# UVLO_MODULE_TOP.net
KiCad netlist of a schematic drawn in Altium Designer
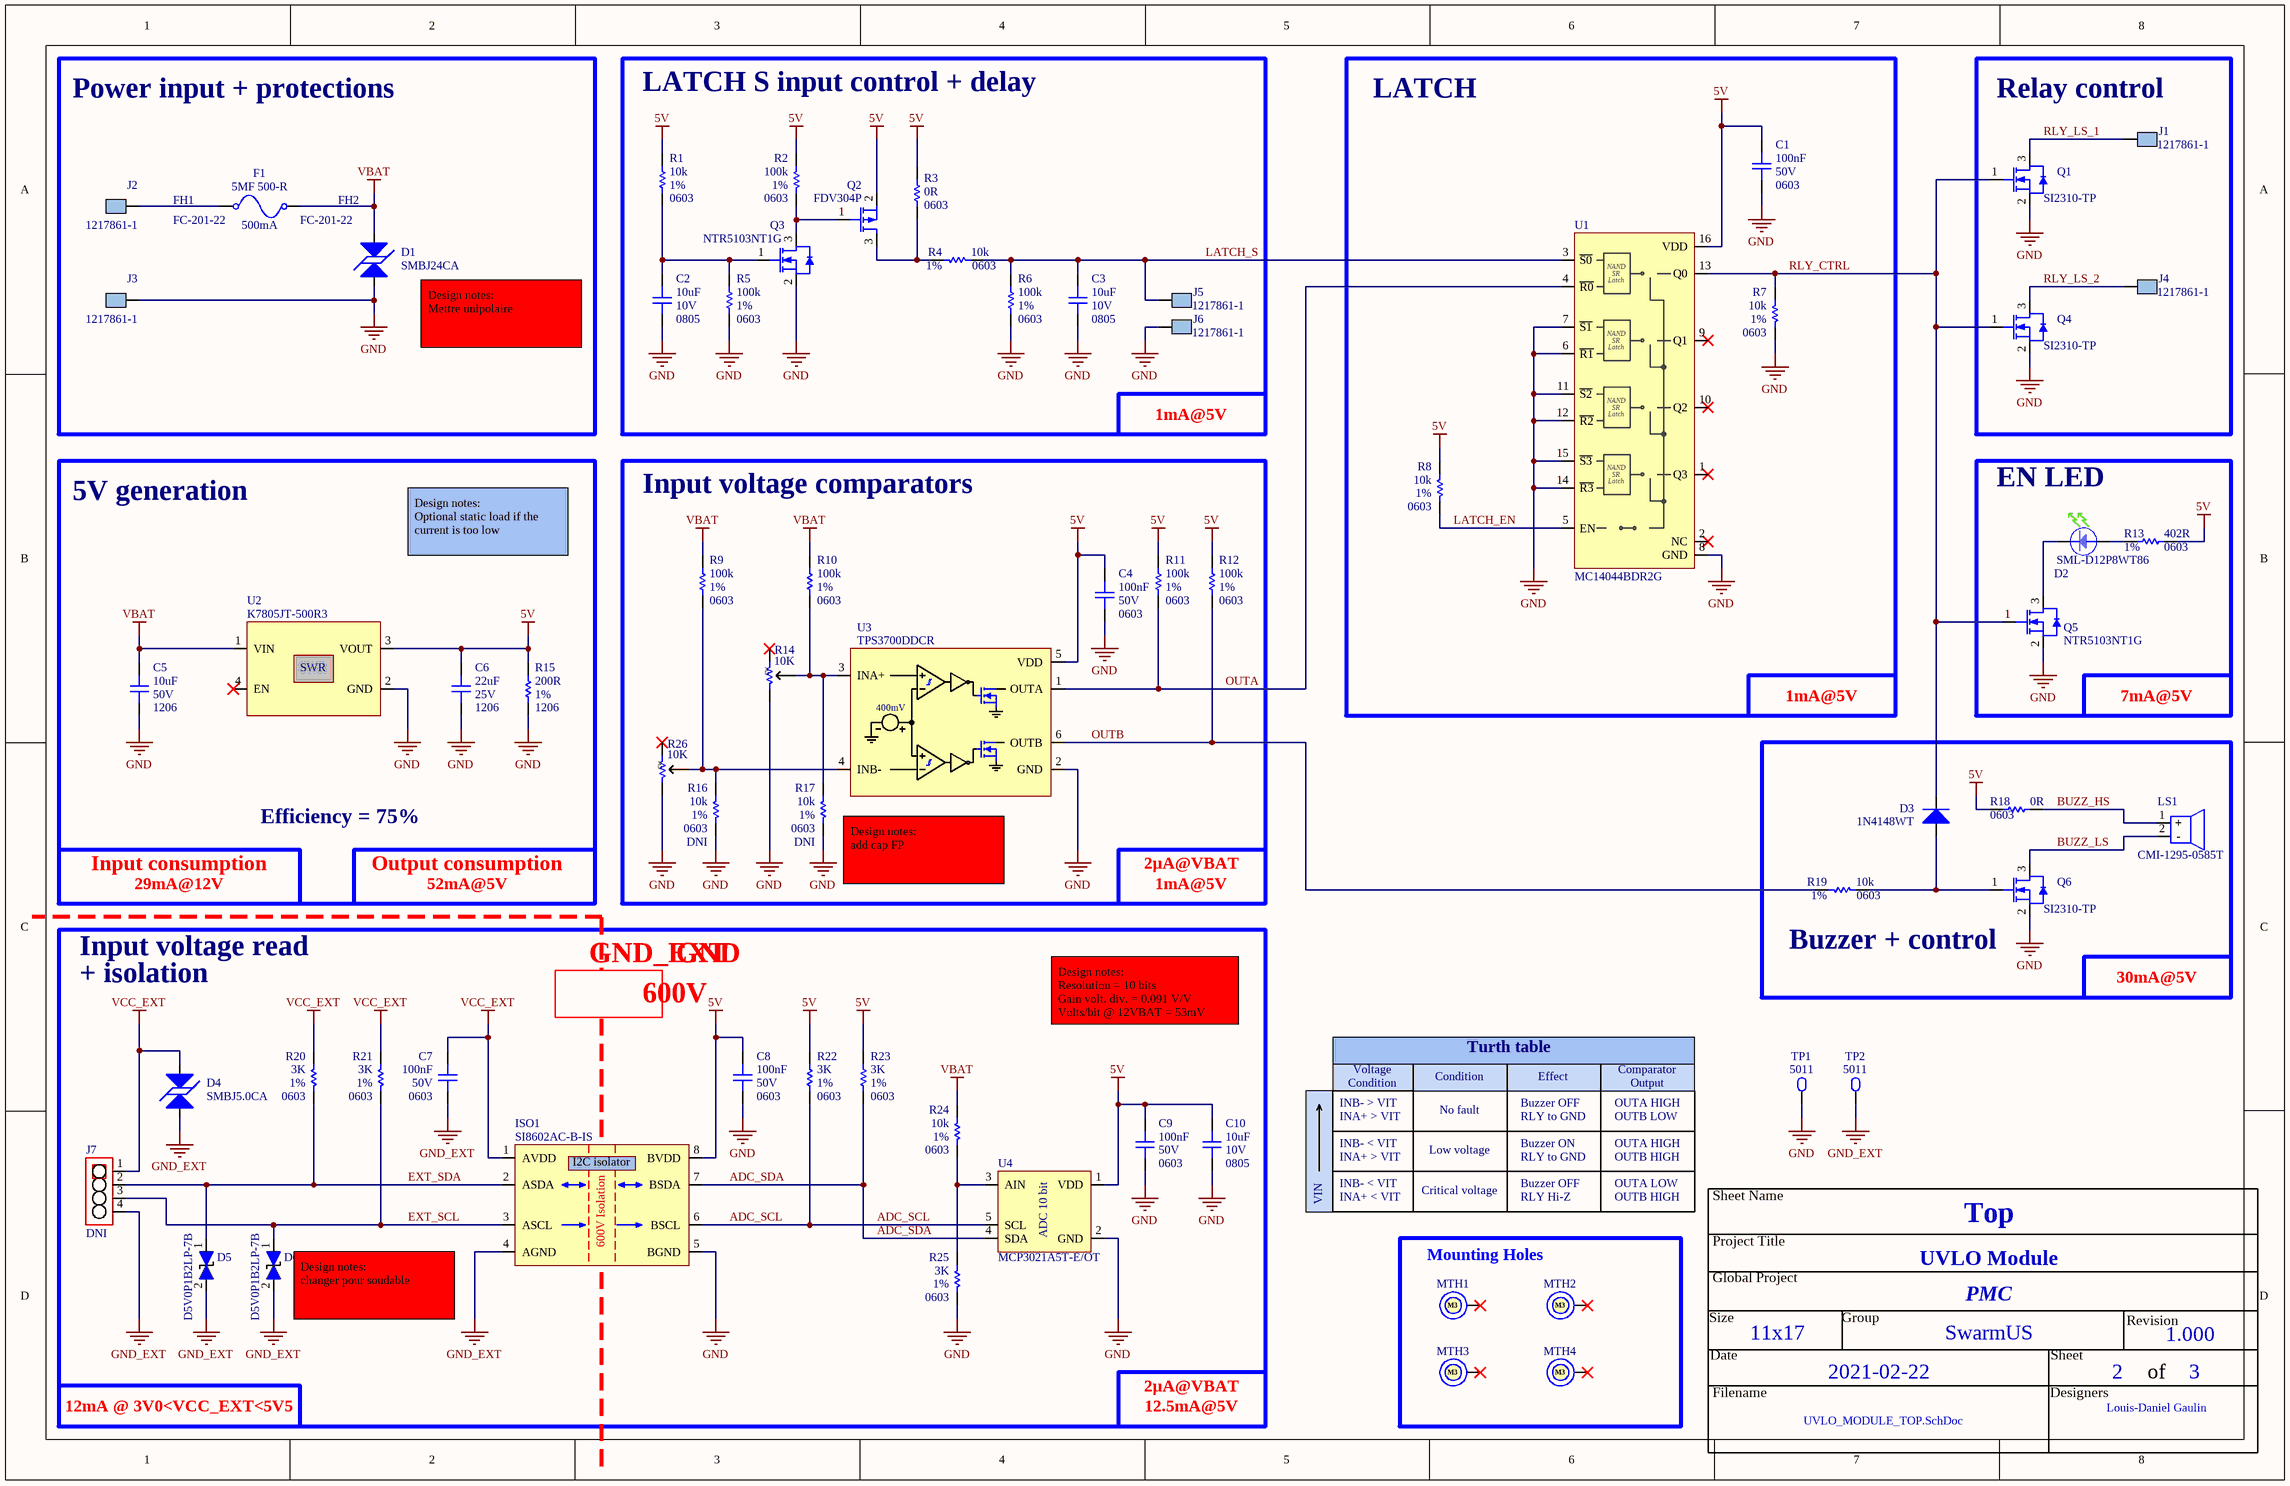
[diagram p0: UVLO_MODULE_TOP.SchDoc]

(export (version "E")
  (design (tool "Eeschema 10.0.6"))
  (components
    (comp (ref "C1")
      (value "100nF")
      (footprint "CAP_CER_0603")
      (description "CAP - CER 100nF 50V X7R - 0603")
      (fields
        (field (name "TOLERANCE") "10%")
        (field (name "PACKAGE") "0603")
        (field (name "VOLTAGE RATING") "50V")
        (field (name "Comment") "CC0603KRX7R9BB104")
        (field (name "CREATEDBY/DATE") "Louis-Daniel Gaulin / 25-02-2021")
        (field (name "VERIFIEDBY") "Hubert Dube - 26/02/2021")
      )
      (libsource (lib "SWARMUS_LIB") (part "CAP_CER_CC0603KRX7R9BB104"))
    )
    (comp (ref "C2")
      (value "10uF")
      (footprint "CAP_CER_0805")
      (description "CAP - CER 10UF 10% 10V X5R - 0805")
      (fields
        (field (name "TOLERANCE") "10%")
        (field (name "PACKAGE") "0805")
        (field (name "VOLTAGE RATING") "10V")
        (field (name "Comment") "LMK212BJ106KG-T")
        (field (name "CREATEDBY/DATE") "Caroline Paulin / 25 juillet 2018")
        (field (name "VERIFIEDBY") "Nicolas V. (2019-01-22)")
      )
      (libsource (lib "GRAMS_MASTER_LIB") (part "CAP_CER_LMK212BJ106KG-T"))
    )
    (comp (ref "C3")
      (value "10uF")
      (footprint "CAP_CER_0805")
      (description "CAP - CER 10UF 10% 10V X5R - 0805")
      (fields
        (field (name "TOLERANCE") "10%")
        (field (name "PACKAGE") "0805")
        (field (name "VOLTAGE RATING") "10V")
        (field (name "Comment") "LMK212BJ106KG-T")
        (field (name "CREATEDBY/DATE") "Caroline Paulin / 25 juillet 2018")
        (field (name "VERIFIEDBY") "Nicolas V. (2019-01-22)")
      )
      (libsource (lib "GRAMS_MASTER_LIB") (part "CAP_CER_LMK212BJ106KG-T"))
    )
    (comp (ref "C4")
      (value "100nF")
      (footprint "CAP_CER_0603")
      (description "CAP - CER 100nF 50V X7R - 0603")
      (fields
        (field (name "TOLERANCE") "10%")
        (field (name "PACKAGE") "0603")
        (field (name "VOLTAGE RATING") "50V")
        (field (name "Comment") "CC0603KRX7R9BB104")
        (field (name "CREATEDBY/DATE") "Louis-Daniel Gaulin / 25-02-2021")
        (field (name "VERIFIEDBY") "Hubert Dube - 26/02/2021")
      )
      (libsource (lib "SWARMUS_LIB") (part "CAP_CER_CC0603KRX7R9BB104"))
    )
    (comp (ref "C5")
      (value "10uF")
      (footprint "CAP_CER_1206")
      (description "CAP - CER 10UF 10% 50V X5R - 1206")
      (fields
        (field (name "TOLERANCE") "10%")
        (field (name "PACKAGE") "1206")
        (field (name "VOLTAGE RATING") "50V")
        (field (name "Comment") "GRT31CR61H106KE01L")
        (field (name "CREATEDBY/DATE") "Nicolas Roy - 2018/12/19")
        (field (name "VERIFIEDBY") "Nicolas V. (2019-01-22)")
      )
      (libsource (lib "GRAMS_MASTER_LIB") (part "CAP_CER_GRT31CR61H106KE01L"))
    )
    (comp (ref "C6")
      (value "22uF")
      (footprint "CAP_CER_1206")
      (description "CAP - CER 22uF 10% 25V X5R - 1206")
      (fields
        (field (name "TOLERANCE") "10%")
        (field (name "PACKAGE") "1206")
        (field (name "VOLTAGE RATING") "25V")
        (field (name "Comment") "CL31A226KAHNNNE")
        (field (name "CREATEDBY/DATE") "Philippe Arsenault/21 Janvier 2020")
        (field (name "VERIFIEDBY") "C.Paulin - 28/01/2020")
      )
      (libsource (lib "GRAMS_MASTER_LIB") (part "CAP_CER_CL31A226KAHNNNE"))
    )
    (comp (ref "C7")
      (value "100nF")
      (footprint "CAP_CER_0603")
      (description "CAP - CER 100nF 50V X7R - 0603")
      (fields
        (field (name "TOLERANCE") "10%")
        (field (name "PACKAGE") "0603")
        (field (name "VOLTAGE RATING") "50V")
        (field (name "Comment") "CC0603KRX7R9BB104")
        (field (name "CREATEDBY/DATE") "Louis-Daniel Gaulin / 25-02-2021")
        (field (name "VERIFIEDBY") "Hubert Dube - 26/02/2021")
      )
      (libsource (lib "SWARMUS_LIB") (part "CAP_CER_CC0603KRX7R9BB104"))
    )
    (comp (ref "C8")
      (value "100nF")
      (footprint "CAP_CER_0603")
      (description "CAP - CER 100nF 50V X7R - 0603")
      (fields
        (field (name "TOLERANCE") "10%")
        (field (name "PACKAGE") "0603")
        (field (name "VOLTAGE RATING") "50V")
        (field (name "Comment") "CC0603KRX7R9BB104")
        (field (name "CREATEDBY/DATE") "Louis-Daniel Gaulin / 25-02-2021")
        (field (name "VERIFIEDBY") "Hubert Dube - 26/02/2021")
      )
      (libsource (lib "SWARMUS_LIB") (part "CAP_CER_CC0603KRX7R9BB104"))
    )
    (comp (ref "C9")
      (value "100nF")
      (footprint "CAP_CER_0603")
      (description "CAP - CER 100nF 50V X7R - 0603")
      (fields
        (field (name "TOLERANCE") "10%")
        (field (name "PACKAGE") "0603")
        (field (name "VOLTAGE RATING") "50V")
        (field (name "Comment") "CC0603KRX7R9BB104")
        (field (name "CREATEDBY/DATE") "Louis-Daniel Gaulin / 25-02-2021")
        (field (name "VERIFIEDBY") "Hubert Dube - 26/02/2021")
      )
      (libsource (lib "SWARMUS_LIB") (part "CAP_CER_CC0603KRX7R9BB104"))
    )
    (comp (ref "C10")
      (value "10uF")
      (footprint "CAP_CER_0805")
      (description "CAP - CER 10UF 10% 10V X5R - 0805")
      (fields
        (field (name "TOLERANCE") "10%")
        (field (name "PACKAGE") "0805")
        (field (name "VOLTAGE RATING") "10V")
        (field (name "Comment") "LMK212BJ106KG-T")
        (field (name "CREATEDBY/DATE") "Caroline Paulin / 25 juillet 2018")
        (field (name "VERIFIEDBY") "Nicolas V. (2019-01-22)")
      )
      (libsource (lib "GRAMS_MASTER_LIB") (part "CAP_CER_LMK212BJ106KG-T"))
    )
    (comp (ref "D1")
      (value "SMBJ24CA")
      (footprint "TVS_PWR_SMBJ36CA")
      (description "TVS - 24V 26.7V 600W - DO214AA")
      (fields
        (field (name "CREATEDBY/DATE") "Arnaud Samson - 06/07/18")
        (field (name "VERIFIEDBY") "Jonathan Bouchard - 2018-07-13")
      )
      (libsource (lib "GRAMS_MASTER_LIB") (part "TVS_PWR_SMBJ24CA"))
    )
    (comp (ref "D2")
      (value "SML-D12P8WT86")
      (footprint "LED_SML-D12P8WT86")
      (description "LED - GREEN DIFFUSED 0603 SMD - 0603")
      (fields
        (field (name "CREATEDBY/DATE") "Keven Deslandes - 2018/11/21")
        (field (name "VERIFIEDBY") "Caroline Paulin - 13 février 2019")
      )
      (libsource (lib "GRAMS_MASTER_LIB") (part "LED_SML-D12P8WT86"))
    )
    (comp (ref "D3")
      (value "1N4148WT")
      (footprint "DIO_1N4148WT")
      (description "DIO - 1N4148WT - SOD-523F")
      (fields
        (field (name "CREATEDBY/DATE") "Joel Lemay 2018-06-15")
        (field (name "VERIFIEDBY") "Arnaud Samson 17-07-18")
      )
      (libsource (lib "GRAMS_MASTER_LIB") (part "DIO_1N4148WT"))
    )
    (comp (ref "D4")
      (value "SMBJ5.0CA")
      (footprint "TVS_PWR_SMBJ5.0CA")
      (description "TVS - BIDIR 5V 9.2V 600W - DO214AA")
      (fields
        (field (name "CREATEDBY/DATE") "Jonathan Bouchard - 2019-03-22")
        (field (name "VERIFIEDBY") "Nicolas V. (2019-05-06)")
      )
      (libsource (lib "GRAMS_MASTER_LIB") (part "TVS_PWR_SMBJ5.0CA"))
    )
    (comp (ref "D5")
      (value "D5V0P1B2LP-7B")
      (footprint "TVS_DATA_D5V0P1B2LP-7B")
      (description "TVS - TVS DIODE 5.5V 13V - 0402")
      (fields
        (field (name "CREATEDBY/DATE") "Keven Deslandes - 2018/10/19")
        (field (name "VERIFIEDBY") "Caroline Paulin -28 janvier 2018")
      )
      (libsource (lib "GRAMS_MASTER_LIB") (part "TVS_DATA_D5V0P1B2LP-7B"))
    )
    (comp (ref "D6")
      (value "D5V0P1B2LP-7B")
      (footprint "TVS_DATA_D5V0P1B2LP-7B")
      (description "TVS - TVS DIODE 5.5V 13V - 0402")
      (fields
        (field (name "CREATEDBY/DATE") "Keven Deslandes - 2018/10/19")
        (field (name "VERIFIEDBY") "Caroline Paulin -28 janvier 2018")
      )
      (libsource (lib "GRAMS_MASTER_LIB") (part "TVS_DATA_D5V0P1B2LP-7B"))
    )
    (comp (ref "F1")
      (value "5MF 500-R")
      (footprint "FUS_5MF 500-R")
      (description "FUS - CARTRIDGE GLASS 500mA 250VAC/125VDC - 5X20mm")
      (fields
        (field (name "CURRENT RATING") "500mA")
        (field (name "CREATEDBY/DATE") "Louis-Daniel Gaulin")
        (field (name "VERIFIEDBY") "Hubert Dube - 26/02/2021")
      )
      (libsource (lib "SWARMUS_LIB") (part "FUS_5MF 500-R"))
    )
    (comp (ref "FH1")
      (value "FC-201-22")
      (footprint "FHO_FC-201-22")
      (description "FHO - FUSE CLIP 5mm CARTRIDGE 10A PCB - 2-TH")
      (fields
        (field (name "CREATEDBY/DATE") "Louis-Daniel Gaulin / 26-02-2021")
        (field (name "VERIFIEDBY") "Hubert Dube - 26/02/2021")
      )
      (libsource (lib "SWARMUS_LIB") (part "FHO_FC-201-22"))
    )
    (comp (ref "FH2")
      (value "FC-201-22")
      (footprint "FHO_FC-201-22")
      (description "FHO - FUSE CLIP 5mm CARTRIDGE 10A PCB - 2-TH")
      (fields
        (field (name "CREATEDBY/DATE") "Louis-Daniel Gaulin / 26-02-2021")
        (field (name "VERIFIEDBY") "Hubert Dube - 26/02/2021")
      )
      (libsource (lib "SWARMUS_LIB") (part "FHO_FC-201-22"))
    )
    (comp (ref "ISO1")
      (value "SI8602AC-B-IS")
      (footprint "ISO_SI8602AC-B-IS")
      (description "ISO - DGTL ISO 600V 2CH I2C  - 8-SOIC")
      (fields
        (field (name "CREATEDBY/DATE") "Louis-Daniel Gaulin / 25-02-2021")
        (field (name "VERIFIEDBY") "Hubert Dube - 26/02/2021")
      )
      (libsource (lib "SWARMUS_LIB") (part "ISO_SI8602AC-B-IS"))
    )
    (comp (ref "J1")
      (value "1217861-1")
      (footprint "CON_1217861-1")
      (description "CON - Quick connect tab - TH")
      (fields
        (field (name "CREATEDBY/DATE") "Louis-Daniel Gaulin / 24-02-2021")
        (field (name "VERIFIEDBY") "Hubert Dube - 26/02/2021")
      )
      (libsource (lib "SWARMUS_LIB") (part "CON_1217861-1"))
    )
    (comp (ref "J2")
      (value "1217861-1")
      (footprint "CON_1217861-1")
      (description "CON - Quick connect tab - TH")
      (fields
        (field (name "CREATEDBY/DATE") "Louis-Daniel Gaulin / 24-02-2021")
        (field (name "VERIFIEDBY") "Hubert Dube - 26/02/2021")
      )
      (libsource (lib "") (part "CON_1217861-1_1"))
    )
    (comp (ref "J3")
      (value "1217861-1")
      (footprint "CON_1217861-1")
      (description "CON - Quick connect tab - TH")
      (fields
        (field (name "CREATEDBY/DATE") "Louis-Daniel Gaulin / 24-02-2021")
        (field (name "VERIFIEDBY") "Hubert Dube - 26/02/2021")
      )
      (libsource (lib "") (part "CON_1217861-1_1"))
    )
    (comp (ref "J4")
      (value "1217861-1")
      (footprint "CON_1217861-1")
      (description "CON - Quick connect tab - TH")
      (fields
        (field (name "CREATEDBY/DATE") "Louis-Daniel Gaulin / 24-02-2021")
        (field (name "VERIFIEDBY") "Hubert Dube - 26/02/2021")
      )
      (libsource (lib "SWARMUS_LIB") (part "CON_1217861-1"))
    )
    (comp (ref "J5")
      (value "1217861-1")
      (footprint "CON_1217861-1")
      (description "CON - Quick connect tab - TH")
      (fields
        (field (name "CREATEDBY/DATE") "Louis-Daniel Gaulin / 24-02-2021")
        (field (name "VERIFIEDBY") "Hubert Dube - 26/02/2021")
      )
      (libsource (lib "SWARMUS_LIB") (part "CON_1217861-1"))
    )
    (comp (ref "J6")
      (value "1217861-1")
      (footprint "CON_1217861-1")
      (description "CON - Quick connect tab - TH")
      (fields
        (field (name "CREATEDBY/DATE") "Louis-Daniel Gaulin / 24-02-2021")
        (field (name "VERIFIEDBY") "Hubert Dube - 26/02/2021")
      )
      (libsource (lib "SWARMUS_LIB") (part "CON_1217861-1"))
    )
    (comp (ref "J7")
      (value "CON_HDR_1X4")
      (footprint "CON_HDR_1X4")
      (description "CON - Header 1X4 pins, 100Mils - TH-4")
      (fields
        (field (name "ASSEMBLY NOTE") "DNI")
        (field (name "CREATEDBY/DATE") "Nicolas V (2020-02-24)")
        (field (name "VERIFIEDBY") "Nicolas V (2020-02-24)")
      )
      (libsource (lib "GRAMS_MASTER_LIB") (part "CON_HDR_1X4"))
    )
    (comp (ref "LS1")
      (value "CMI-1295-0585T")
      (footprint "UND_SPK_CMI-1295-0585T")
      (description "LS - Buzzer indicator 5V 30mA 2.3kHz 85dB - TH")
      (fields
        (field (name "CREATEDBY/DATE") "Louis-Daniel Gaulin / 24-02-2021")
        (field (name "VERIFIEDBY") "Hubert Dube - 26/02/2021")
      )
      (libsource (lib "SWARMUS_LIB") (part "UND_LS_CMI-1295-0585T"))
    )
    (comp (ref "MTH1")
      (value "M3")
      (footprint "MTH_M3")
      (description "MTH - MOUNTING HOLE M3 PLATED - M3")
      (fields
        (field (name "CREATEDBY/DATE") "Jonathan Bouchard 2018-07-23")
        (field (name "VERIFIEDBY") "Arnaud Samson 23-07-18")
      )
      (libsource (lib "GRAMS_MASTER_LIB") (part "MTH_M3"))
    )
    (comp (ref "MTH2")
      (value "M3")
      (footprint "MTH_M3")
      (description "MTH - MOUNTING HOLE M3 PLATED - M3")
      (fields
        (field (name "CREATEDBY/DATE") "Jonathan Bouchard 2018-07-23")
        (field (name "VERIFIEDBY") "Arnaud Samson 23-07-18")
      )
      (libsource (lib "GRAMS_MASTER_LIB") (part "MTH_M3"))
    )
    (comp (ref "MTH3")
      (value "M3")
      (footprint "MTH_M3")
      (description "MTH - MOUNTING HOLE M3 PLATED - M3")
      (fields
        (field (name "CREATEDBY/DATE") "Jonathan Bouchard 2018-07-23")
        (field (name "VERIFIEDBY") "Arnaud Samson 23-07-18")
      )
      (libsource (lib "GRAMS_MASTER_LIB") (part "MTH_M3"))
    )
    (comp (ref "MTH4")
      (value "M3")
      (footprint "MTH_M3")
      (description "MTH - MOUNTING HOLE M3 PLATED - M3")
      (fields
        (field (name "CREATEDBY/DATE") "Jonathan Bouchard 2018-07-23")
        (field (name "VERIFIEDBY") "Arnaud Samson 23-07-18")
      )
      (libsource (lib "GRAMS_MASTER_LIB") (part "MTH_M3"))
    )
    (comp (ref "Q1")
      (value "SI2310-TP")
      (footprint "TRX_NMOS_SI2310-TP")
      (description "TRX - MOSFET N-CH 60V 3A - SOT-23")
      (fields
        (field (name "CREATEDBY/DATE") "Louis-Daniel Gaulin / 20-02-2020")
        (field (name "VERIFIEDBY") "C.Paulin - 21/02/2020")
      )
      (libsource (lib "GRAMS_MASTER_LIB") (part "TRX_NMOS_SI2310-TP"))
    )
    (comp (ref "Q2")
      (value "FDV304P")
      (footprint "TRX_PMOS_FDV304P")
      (description "TRX - PMOS 25V 460MA - SOT−23")
      (fields
        (field (name "CREATEDBY/DATE") "Joel Lemay 2018-07-20")
        (field (name "VERIFIEDBY") "Caroline Paulin - 6 sept 2018")
      )
      (libsource (lib "GRAMS_MASTER_LIB") (part "TRX_PMOS_FDV304P"))
    )
    (comp (ref "Q3")
      (value "NTR5103NT1G")
      (footprint "TRX_NMOS_NTR5103NT1G")
      (description "TRX - MOSFET N-CH 60V 0.26A- SOT-23-3")
      (fields
        (field (name "CREATEDBY/DATE") "Olivier Bernard / 7/5/2017")
        (field (name "VERIFIEDBY") "Caroline Paulin / 10 juillet 2018")
      )
      (libsource (lib "GRAMS_MASTER_LIB") (part "TRX_NMOS_NTR5103NT1G"))
    )
    (comp (ref "Q4")
      (value "SI2310-TP")
      (footprint "TRX_NMOS_SI2310-TP")
      (description "TRX - MOSFET N-CH 60V 3A - SOT-23")
      (fields
        (field (name "CREATEDBY/DATE") "Louis-Daniel Gaulin / 20-02-2020")
        (field (name "VERIFIEDBY") "C.Paulin - 21/02/2020")
      )
      (libsource (lib "GRAMS_MASTER_LIB") (part "TRX_NMOS_SI2310-TP"))
    )
    (comp (ref "Q5")
      (value "NTR5103NT1G")
      (footprint "TRX_NMOS_NTR5103NT1G")
      (description "TRX - MOSFET N-CH 60V 0.26A- SOT-23-3")
      (fields
        (field (name "CREATEDBY/DATE") "Olivier Bernard / 7/5/2017")
        (field (name "VERIFIEDBY") "Caroline Paulin / 10 juillet 2018")
      )
      (libsource (lib "GRAMS_MASTER_LIB") (part "TRX_NMOS_NTR5103NT1G"))
    )
    (comp (ref "Q6")
      (value "SI2310-TP")
      (footprint "TRX_NMOS_SI2310-TP")
      (description "TRX - MOSFET N-CH 60V 3A - SOT-23")
      (fields
        (field (name "CREATEDBY/DATE") "Louis-Daniel Gaulin / 20-02-2020")
        (field (name "VERIFIEDBY") "C.Paulin - 21/02/2020")
      )
      (libsource (lib "GRAMS_MASTER_LIB") (part "TRX_NMOS_SI2310-TP"))
    )
    (comp (ref "R1")
      (value "10k")
      (footprint "RES_0603")
      (description "RES - 10k 1% 1/10W - 0603")
      (fields
        (field (name "TOLERANCE") "1%")
        (field (name "PACKAGE") "0603")
        (field (name "Comment") "RC0603FR-0710KL")
        (field (name "CREATEDBY/DATE") "Louis-Daniel Gaulin / 24-02-2021")
        (field (name "VERIFIEDBY") "Hubert Dube - 26/02/2021")
      )
      (libsource (lib "SWARMUS_LIB") (part "RES_RC0603FR-0710KL"))
    )
    (comp (ref "R2")
      (value "100k")
      (footprint "RES_0603")
      (description "RES - 100k 1% 1/10W - 0603")
      (fields
        (field (name "TOLERANCE") "1%")
        (field (name "PACKAGE") "0603")
        (field (name "Comment") "RC0603FR-07100KL")
        (field (name "CREATEDBY/DATE") "Louis-Daniel Gaulin / 24-02-2021")
        (field (name "VERIFIEDBY") "Hubert Dube")
      )
      (libsource (lib "SWARMUS_LIB") (part "RES_RC0603FR-07100KL"))
    )
    (comp (ref "R3")
      (value "0R")
      (footprint "RES_0603")
      (description "RES - 0 ohm jumper 1/10W - 0603")
      (fields
        (field (name "PACKAGE") "0603")
        (field (name "Comment") "RC0603JR-070RL")
        (field (name "CREATEDBY/DATE") "L-P Gauthier 2018-10-30")
        (field (name "VERIFIEDBY") "Caroline Paulin  - 5/11/2018")
      )
      (libsource (lib "GRAMS_MASTER_LIB") (part "RES_RC0603JR-070RL"))
    )
    (comp (ref "R4")
      (value "10k")
      (footprint "RES_0603")
      (description "RES - 10k 1% 1/10W - 0603")
      (fields
        (field (name "TOLERANCE") "1%")
        (field (name "PACKAGE") "0603")
        (field (name "Comment") "RC0603FR-0710KL")
        (field (name "CREATEDBY/DATE") "Louis-Daniel Gaulin / 24-02-2021")
        (field (name "VERIFIEDBY") "Hubert Dube - 26/02/2021")
      )
      (libsource (lib "SWARMUS_LIB") (part "RES_RC0603FR-0710KL"))
    )
    (comp (ref "R5")
      (value "100k")
      (footprint "RES_0603")
      (description "RES - 100k 1% 1/10W - 0603")
      (fields
        (field (name "TOLERANCE") "1%")
        (field (name "PACKAGE") "0603")
        (field (name "Comment") "RC0603FR-07100KL")
        (field (name "CREATEDBY/DATE") "Louis-Daniel Gaulin / 24-02-2021")
        (field (name "VERIFIEDBY") "Hubert Dube")
      )
      (libsource (lib "SWARMUS_LIB") (part "RES_RC0603FR-07100KL"))
    )
    (comp (ref "R6")
      (value "100k")
      (footprint "RES_0603")
      (description "RES - 100k 1% 1/10W - 0603")
      (fields
        (field (name "TOLERANCE") "1%")
        (field (name "PACKAGE") "0603")
        (field (name "Comment") "RC0603FR-07100KL")
        (field (name "CREATEDBY/DATE") "Louis-Daniel Gaulin / 24-02-2021")
        (field (name "VERIFIEDBY") "Hubert Dube")
      )
      (libsource (lib "SWARMUS_LIB") (part "RES_RC0603FR-07100KL"))
    )
    (comp (ref "R7")
      (value "10k")
      (footprint "RES_0603")
      (description "RES - 10k 1% 1/10W - 0603")
      (fields
        (field (name "TOLERANCE") "1%")
        (field (name "PACKAGE") "0603")
        (field (name "Comment") "RC0603FR-0710KL")
        (field (name "CREATEDBY/DATE") "Louis-Daniel Gaulin / 24-02-2021")
        (field (name "VERIFIEDBY") "Hubert Dube - 26/02/2021")
      )
      (libsource (lib "SWARMUS_LIB") (part "RES_RC0603FR-0710KL"))
    )
    (comp (ref "R8")
      (value "10k")
      (footprint "RES_0603")
      (description "RES - 10k 1% 1/10W - 0603")
      (fields
        (field (name "TOLERANCE") "1%")
        (field (name "PACKAGE") "0603")
        (field (name "Comment") "RC0603FR-0710KL")
        (field (name "CREATEDBY/DATE") "Louis-Daniel Gaulin / 24-02-2021")
        (field (name "VERIFIEDBY") "Hubert Dube - 26/02/2021")
      )
      (libsource (lib "SWARMUS_LIB") (part "RES_RC0603FR-0710KL"))
    )
    (comp (ref "R9")
      (value "100k")
      (footprint "RES_0603")
      (description "RES - 100k 1% 1/10W - 0603")
      (fields
        (field (name "TOLERANCE") "1%")
        (field (name "PACKAGE") "0603")
        (field (name "Comment") "RC0603FR-07100KL")
        (field (name "CREATEDBY/DATE") "Louis-Daniel Gaulin / 24-02-2021")
        (field (name "VERIFIEDBY") "Hubert Dube")
      )
      (libsource (lib "SWARMUS_LIB") (part "RES_RC0603FR-07100KL"))
    )
    (comp (ref "R10")
      (value "100k")
      (footprint "RES_0603")
      (description "RES - 100k 1% 1/10W - 0603")
      (fields
        (field (name "TOLERANCE") "1%")
        (field (name "PACKAGE") "0603")
        (field (name "Comment") "RC0603FR-07100KL")
        (field (name "CREATEDBY/DATE") "Louis-Daniel Gaulin / 24-02-2021")
        (field (name "VERIFIEDBY") "Hubert Dube")
      )
      (libsource (lib "SWARMUS_LIB") (part "RES_RC0603FR-07100KL"))
    )
    (comp (ref "R11")
      (value "100k")
      (footprint "RES_0603")
      (description "RES - 100k 1% 1/10W - 0603")
      (fields
        (field (name "TOLERANCE") "1%")
        (field (name "PACKAGE") "0603")
        (field (name "Comment") "RC0603FR-07100KL")
        (field (name "CREATEDBY/DATE") "Louis-Daniel Gaulin / 24-02-2021")
        (field (name "VERIFIEDBY") "Hubert Dube")
      )
      (libsource (lib "SWARMUS_LIB") (part "RES_RC0603FR-07100KL"))
    )
    (comp (ref "R12")
      (value "100k")
      (footprint "RES_0603")
      (description "RES - 100k 1% 1/10W - 0603")
      (fields
        (field (name "TOLERANCE") "1%")
        (field (name "PACKAGE") "0603")
        (field (name "Comment") "RC0603FR-07100KL")
        (field (name "CREATEDBY/DATE") "Louis-Daniel Gaulin / 24-02-2021")
        (field (name "VERIFIEDBY") "Hubert Dube")
      )
      (libsource (lib "SWARMUS_LIB") (part "RES_RC0603FR-07100KL"))
    )
    (comp (ref "R13")
      (value "402R")
      (footprint "RES_0603")
      (description "RES - 402R 1% 1/10W - 0603")
      (fields
        (field (name "TOLERANCE") "1%")
        (field (name "PACKAGE") "0603")
        (field (name "Comment") "RC0603FR-07402RL")
        (field (name "CREATEDBY/DATE") "Louis-Daniel Gaulin / 24-02-2021")
        (field (name "VERIFIEDBY") "Hubert Dube - 26/02/2021")
      )
      (libsource (lib "SWARMUS_LIB") (part "RES_RC0603FR-07402RL"))
    )
    (comp (ref "R14")
      (value "10K")
      (footprint "POT_3362P-1-103LF")
      (description "RES -  POT 10K 1/2W LINEAR PLASTIC 1 turn - TH")
      (fields
        (field (name "TOLERANCE") "10%")
        (field (name "Comment") "3362P-1-103LF")
        (field (name "CREATEDBY/DATE") "Louis-Daniel Gaulin / 24-02-2021")
        (field (name "VERIFIEDBY") "Hubert Dube - 26/02/2021")
      )
      (libsource (lib "SWARMUS_LIB") (part "POT_3362P-1-103LF"))
    )
    (comp (ref "R15")
      (value "200R")
      (footprint "RES_1206")
      (description "RES - 200R 1% 1/4W - 1206")
      (fields
        (field (name "TOLERANCE") "1%")
        (field (name "PACKAGE") "1206")
        (field (name "Comment") "CRCW1206200RFKEAC")
        (field (name "CREATEDBY/DATE") "Louis-Daniel Gaulin / 26-02-2021")
        (field (name "VERIFIEDBY") "Hubert Dubé/ 26-02-2021")
      )
      (libsource (lib "SWARMUS_LIB") (part "RES_CRCW1206200RFKEAC"))
    )
    (comp (ref "R16")
      (value "10k")
      (footprint "RES_0603")
      (description "RES - 10k 1% 1/10W - 0603")
      (fields
        (field (name "ASSEMBLY NOTE") "DNI")
        (field (name "TOLERANCE") "1%")
        (field (name "PACKAGE") "0603")
        (field (name "Comment") "RC0603FR-0710KL")
        (field (name "CREATEDBY/DATE") "Louis-Daniel Gaulin / 24-02-2021")
        (field (name "VERIFIEDBY") "Hubert Dube - 26/02/2021")
      )
      (libsource (lib "SWARMUS_LIB") (part "RES_RC0603FR-0710KL"))
    )
    (comp (ref "R17")
      (value "10k")
      (footprint "RES_0603")
      (description "RES - 10k 1% 1/10W - 0603")
      (fields
        (field (name "ASSEMBLY NOTE") "DNI")
        (field (name "TOLERANCE") "1%")
        (field (name "PACKAGE") "0603")
        (field (name "Comment") "RC0603FR-0710KL")
        (field (name "CREATEDBY/DATE") "Louis-Daniel Gaulin / 24-02-2021")
        (field (name "VERIFIEDBY") "Hubert Dube - 26/02/2021")
      )
      (libsource (lib "SWARMUS_LIB") (part "RES_RC0603FR-0710KL"))
    )
    (comp (ref "R18")
      (value "0R")
      (footprint "RES_0603")
      (description "RES - 0 ohm jumper 1/10W - 0603")
      (fields
        (field (name "PACKAGE") "0603")
        (field (name "Comment") "RC0603JR-070RL")
        (field (name "CREATEDBY/DATE") "L-P Gauthier 2018-10-30")
        (field (name "VERIFIEDBY") "Caroline Paulin  - 5/11/2018")
      )
      (libsource (lib "GRAMS_MASTER_LIB") (part "RES_RC0603JR-070RL"))
    )
    (comp (ref "R19")
      (value "10k")
      (footprint "RES_0603")
      (description "RES - 10k 1% 1/10W - 0603")
      (fields
        (field (name "TOLERANCE") "1%")
        (field (name "PACKAGE") "0603")
        (field (name "Comment") "RC0603FR-0710KL")
        (field (name "CREATEDBY/DATE") "Louis-Daniel Gaulin / 24-02-2021")
        (field (name "VERIFIEDBY") "Hubert Dube - 26/02/2021")
      )
      (libsource (lib "SWARMUS_LIB") (part "RES_RC0603FR-0710KL"))
    )
    (comp (ref "R20")
      (value "3K")
      (footprint "RES_0603")
      (description "RES - 3k 1% 1/10W - 0603")
      (fields
        (field (name "TOLERANCE") "1%")
        (field (name "PACKAGE") "0603")
        (field (name "Comment") "RC0603FR-073KL")
        (field (name "CREATEDBY/DATE") "Louis-Daniel Gaulin / 24-02-2021")
        (field (name "VERIFIEDBY") "Hubert Dube - 26/02/2021")
      )
      (libsource (lib "SWARMUS_LIB") (part "RES_RC0603FR-073KL"))
    )
    (comp (ref "R21")
      (value "3K")
      (footprint "RES_0603")
      (description "RES - 3k 1% 1/10W - 0603")
      (fields
        (field (name "TOLERANCE") "1%")
        (field (name "PACKAGE") "0603")
        (field (name "Comment") "RC0603FR-073KL")
        (field (name "CREATEDBY/DATE") "Louis-Daniel Gaulin / 24-02-2021")
        (field (name "VERIFIEDBY") "Hubert Dube - 26/02/2021")
      )
      (libsource (lib "SWARMUS_LIB") (part "RES_RC0603FR-073KL"))
    )
    (comp (ref "R22")
      (value "3K")
      (footprint "RES_0603")
      (description "RES - 3k 1% 1/10W - 0603")
      (fields
        (field (name "TOLERANCE") "1%")
        (field (name "PACKAGE") "0603")
        (field (name "Comment") "RC0603FR-073KL")
        (field (name "CREATEDBY/DATE") "Louis-Daniel Gaulin / 24-02-2021")
        (field (name "VERIFIEDBY") "Hubert Dube - 26/02/2021")
      )
      (libsource (lib "SWARMUS_LIB") (part "RES_RC0603FR-073KL"))
    )
    (comp (ref "R23")
      (value "3K")
      (footprint "RES_0603")
      (description "RES - 3k 1% 1/10W - 0603")
      (fields
        (field (name "TOLERANCE") "1%")
        (field (name "PACKAGE") "0603")
        (field (name "Comment") "RC0603FR-073KL")
        (field (name "CREATEDBY/DATE") "Louis-Daniel Gaulin / 24-02-2021")
        (field (name "VERIFIEDBY") "Hubert Dube - 26/02/2021")
      )
      (libsource (lib "SWARMUS_LIB") (part "RES_RC0603FR-073KL"))
    )
    (comp (ref "R24")
      (value "10k")
      (footprint "RES_0603")
      (description "RES - 10k 1% 1/10W - 0603")
      (fields
        (field (name "TOLERANCE") "1%")
        (field (name "PACKAGE") "0603")
        (field (name "Comment") "RC0603FR-0710KL")
        (field (name "CREATEDBY/DATE") "Louis-Daniel Gaulin / 24-02-2021")
        (field (name "VERIFIEDBY") "Hubert Dube - 26/02/2021")
      )
      (libsource (lib "SWARMUS_LIB") (part "RES_RC0603FR-0710KL"))
    )
    (comp (ref "R25")
      (value "3K")
      (footprint "RES_0603")
      (description "RES - 3k 1% 1/10W - 0603")
      (fields
        (field (name "TOLERANCE") "1%")
        (field (name "PACKAGE") "0603")
        (field (name "Comment") "RC0603FR-073KL")
        (field (name "CREATEDBY/DATE") "Louis-Daniel Gaulin / 24-02-2021")
        (field (name "VERIFIEDBY") "Hubert Dube - 26/02/2021")
      )
      (libsource (lib "SWARMUS_LIB") (part "RES_RC0603FR-073KL"))
    )
    (comp (ref "R26")
      (value "10K")
      (footprint "POT_3362P-1-103LF")
      (description "RES -  POT 10K 1/2W LINEAR PLASTIC 1 turn - TH")
      (fields
        (field (name "TOLERANCE") "10%")
        (field (name "Comment") "3362P-1-103LF")
        (field (name "CREATEDBY/DATE") "Louis-Daniel Gaulin / 24-02-2021")
        (field (name "VERIFIEDBY") "Hubert Dube - 26/02/2021")
      )
      (libsource (lib "SWARMUS_LIB") (part "POT_3362P-1-103LF"))
    )
    (comp (ref "TP1")
      (value "5011")
      (footprint "TPO_5011")
      (description "TPO - TEST POINT - TH")
      (fields
        (field (name "CREATEDBY/DATE") "Louis-Daniel Gauli / 02-11-2020")
        (field (name "VERIFIEDBY") "Philippe Arsenault/2020-11-06")
      )
      (libsource (lib "SWARMUS_LIB") (part "TPO_5011"))
    )
    (comp (ref "TP2")
      (value "5011")
      (footprint "TPO_5011")
      (description "TPO - TEST POINT - TH")
      (fields
        (field (name "CREATEDBY/DATE") "Louis-Daniel Gauli / 02-11-2020")
        (field (name "VERIFIEDBY") "Philippe Arsenault/2020-11-06")
      )
      (libsource (lib "SWARMUS_LIB") (part "TPO_5011"))
    )
    (comp (ref "U1")
      (value "MC14044BDR2G")
      (footprint "LOG_LATCH_MC14044BDR2G")
      (description "LOG - Quad S-R Latch w/ Output Enable - 16-SOIC")
      (fields
        (field (name "CREATEDBY/DATE") "Louis-Daniel Gaulin / 24-02-2021")
        (field (name "VERIFIEDBY") "Hubert Dube - 26/02/2021")
      )
      (libsource (lib "SWARMUS_LIB") (part "LOG_LATCH_MC14044BDR2G"))
    )
    (comp (ref "U2")
      (value "K7805JT-500R3")
      (footprint "REG_SWR_K7805JT-500R3")
      (description "REG_DC DC CONVERTER 5V 2.5W - 4-SMD Module")
      (fields
        (field (name "CREATEDBY/DATE") "Louis-Daniel Gaulin / 25-02-2021")
        (field (name "VERIFIEDBY") "Hubert Dube - 26/02/2021")
      )
      (libsource (lib "SWARMUS_LIB") (part "REG_SWR_K7805JT-500R3"))
    )
    (comp (ref "U3")
      (value "TPS3700DDCR")
      (footprint "CMP_TPS3700DDCR")
      (description "CMP - Comparator Window Open Drain - TSOT-23-6")
      (fields
        (field (name "CREATEDBY/DATE") "Louis-Daniel Gaulin / 22-02-2021")
        (field (name "VERIFIEDBY") "Hubert Dube - 26/02/2021")
      )
      (libsource (lib "SWARMUS_LIB") (part "CMP_TPS3700DDCR"))
    )
    (comp (ref "U4")
      (value "MCP3021A5T-E/OT")
      (footprint "ADC_MCP3021A5T-E/OT")
      (description "ADC - IC ADC 10BIT I2C 22.3KSPS - SOT-23-5")
      (fields
        (field (name "CREATEDBY/DATE") "Louis-Daniel Gaulin / 24-02-2021")
        (field (name "VERIFIEDBY") "Hubert Dube - 26/02/2021")
      )
      (libsource (lib "SWARMUS_LIB") (part "ADC_MCP3021A5T-E/OT"))
    )
  )
  (nets
    (net (code "1") (name "/ADC_SCL") (class "Default")
      (node (ref "ISO1") (pin "6") (pinfunction "BSCL_6") (pintype "passive"))
      (node (ref "R22") (pin "1") (pinfunction "1_1") (pintype "passive"))
      (node (ref "U4") (pin "5") (pinfunction "SCL_5") (pintype "passive"))
    )
    (net (code "2") (name "/ADC_SDA") (class "Default")
      (node (ref "ISO1") (pin "7") (pinfunction "BSDA_7") (pintype "passive"))
      (node (ref "R23") (pin "1") (pinfunction "1_1") (pintype "passive"))
      (node (ref "U4") (pin "4") (pinfunction "SDA_4") (pintype "passive"))
    )
    (net (code "3") (name "/BUZZ_HS") (class "Default")
      (node (ref "LS1") (pin "1") (pinfunction "+_1") (pintype "passive"))
      (node (ref "R18") (pin "1") (pinfunction "1_1") (pintype "passive"))
    )
    (net (code "4") (name "/BUZZ_LS") (class "Default")
      (node (ref "LS1") (pin "2") (pinfunction "-_2") (pintype "passive"))
      (node (ref "Q6") (pin "3") (pinfunction "D_3") (pintype "passive"))
    )
    (net (code "5") (name "/EXT_SCL") (class "Default")
      (node (ref "D6") (pin "1") (pinfunction "i/o_1") (pintype "passive"))
      (node (ref "ISO1") (pin "3") (pinfunction "ASCL_3") (pintype "passive"))
      (node (ref "J7") (pin "3") (pinfunction "3_3") (pintype "passive"))
      (node (ref "R21") (pin "1") (pinfunction "1_1") (pintype "passive"))
    )
    (net (code "6") (name "/EXT_SDA") (class "Default")
      (node (ref "D5") (pin "1") (pinfunction "i/o_1") (pintype "passive"))
      (node (ref "ISO1") (pin "2") (pinfunction "ASDA_2") (pintype "passive"))
      (node (ref "J7") (pin "2") (pinfunction "2_2") (pintype "passive"))
      (node (ref "R20") (pin "1") (pinfunction "1_1") (pintype "passive"))
    )
    (net (code "7") (name "/LATCH_EN") (class "Default")
      (node (ref "R8") (pin "1") (pinfunction "1_1") (pintype "passive"))
      (node (ref "U1") (pin "5") (pinfunction "EN_5") (pintype "passive"))
    )
    (net (code "8") (name "/LATCH_S") (class "Default")
      (node (ref "C3") (pin "2") (pinfunction "2_2") (pintype "passive"))
      (node (ref "J5") (pin "1") (pintype "passive"))
      (node (ref "R4") (pin "1") (pinfunction "1_1") (pintype "passive"))
      (node (ref "R6") (pin "2") (pinfunction "2_2") (pintype "passive"))
      (node (ref "U1") (pin "3") (pinfunction "S0_3") (pintype "passive"))
    )
    (net (code "9") (name "/OUTA") (class "Default")
      (node (ref "R11") (pin "1") (pinfunction "1_1") (pintype "passive"))
      (node (ref "U1") (pin "4") (pinfunction "R0_4") (pintype "passive"))
      (node (ref "U3") (pin "1") (pinfunction "OUTA_1") (pintype "passive"))
    )
    (net (code "10") (name "/OUTB") (class "Default")
      (node (ref "R12") (pin "1") (pinfunction "1_1") (pintype "passive"))
      (node (ref "R19") (pin "2") (pinfunction "2_2") (pintype "passive"))
      (node (ref "U3") (pin "6") (pinfunction "OUTB_6") (pintype "passive"))
    )
    (net (code "11") (name "/RLY_CTRL") (class "Default")
      (node (ref "D3") (pin "K") (pinfunction "K_K") (pintype "passive"))
      (node (ref "Q1") (pin "1") (pinfunction "G_1") (pintype "passive"))
      (node (ref "Q4") (pin "1") (pinfunction "G_1") (pintype "passive"))
      (node (ref "Q5") (pin "1") (pinfunction "G_1") (pintype "passive"))
      (node (ref "R7") (pin "2") (pinfunction "2_2") (pintype "passive"))
      (node (ref "U1") (pin "13") (pinfunction "Q0_13") (pintype "passive"))
    )
    (net (code "12") (name "/RLY_LS_1") (class "Default")
      (node (ref "J1") (pin "1") (pintype "passive"))
      (node (ref "Q1") (pin "3") (pinfunction "D_3") (pintype "passive"))
    )
    (net (code "13") (name "/RLY_LS_2") (class "Default")
      (node (ref "J4") (pin "1") (pintype "passive"))
      (node (ref "Q4") (pin "3") (pinfunction "D_3") (pintype "passive"))
    )
    (net (code "14") (name "5V") (class "Default")
      (node (ref "C1") (pin "2") (pinfunction "2_2") (pintype "passive"))
      (node (ref "C10") (pin "2") (pinfunction "2_2") (pintype "passive"))
      (node (ref "C4") (pin "2") (pinfunction "2_2") (pintype "passive"))
      (node (ref "C6") (pin "2") (pinfunction "2_2") (pintype "passive"))
      (node (ref "C8") (pin "2") (pinfunction "2_2") (pintype "passive"))
      (node (ref "C9") (pin "2") (pinfunction "2_2") (pintype "passive"))
      (node (ref "ISO1") (pin "8") (pinfunction "BVDD_8") (pintype "passive"))
      (node (ref "Q2") (pin "2") (pinfunction "S_2") (pintype "passive"))
      (node (ref "R1") (pin "2") (pinfunction "2_2") (pintype "passive"))
      (node (ref "R11") (pin "2") (pinfunction "2_2") (pintype "passive"))
      (node (ref "R12") (pin "2") (pinfunction "2_2") (pintype "passive"))
      (node (ref "R13") (pin "1") (pinfunction "1_1") (pintype "passive"))
      (node (ref "R15") (pin "2") (pinfunction "2_2") (pintype "passive"))
      (node (ref "R18") (pin "2") (pinfunction "2_2") (pintype "passive"))
      (node (ref "R2") (pin "2") (pinfunction "2_2") (pintype "passive"))
      (node (ref "R22") (pin "2") (pinfunction "2_2") (pintype "passive"))
      (node (ref "R23") (pin "2") (pinfunction "2_2") (pintype "passive"))
      (node (ref "R3") (pin "2") (pinfunction "2_2") (pintype "passive"))
      (node (ref "R8") (pin "2") (pinfunction "2_2") (pintype "passive"))
      (node (ref "U1") (pin "16") (pinfunction "VDD_16") (pintype "passive"))
      (node (ref "U2") (pin "3") (pinfunction "VOUT_3") (pintype "passive"))
      (node (ref "U3") (pin "5") (pinfunction "VDD_5") (pintype "passive"))
      (node (ref "U4") (pin "1") (pinfunction "VDD_1") (pintype "passive"))
    )
    (net (code "15") (name "GND") (class "Default")
      (node (ref "C1") (pin "1") (pinfunction "1_1") (pintype "passive"))
      (node (ref "C10") (pin "1") (pinfunction "1_1") (pintype "passive"))
      (node (ref "C2") (pin "1") (pinfunction "1_1") (pintype "passive"))
      (node (ref "C3") (pin "1") (pinfunction "1_1") (pintype "passive"))
      (node (ref "C4") (pin "1") (pinfunction "1_1") (pintype "passive"))
      (node (ref "C5") (pin "1") (pinfunction "1_1") (pintype "passive"))
      (node (ref "C6") (pin "1") (pinfunction "1_1") (pintype "passive"))
      (node (ref "C8") (pin "1") (pinfunction "1_1") (pintype "passive"))
      (node (ref "C9") (pin "1") (pinfunction "1_1") (pintype "passive"))
      (node (ref "D1") (pin "2") (pinfunction "2_2") (pintype "passive"))
      (node (ref "ISO1") (pin "5") (pinfunction "BGND_5") (pintype "passive"))
      (node (ref "J3") (pin "1") (pintype "passive"))
      (node (ref "J6") (pin "1") (pintype "passive"))
      (node (ref "Q1") (pin "2") (pinfunction "S_2") (pintype "passive"))
      (node (ref "Q3") (pin "2") (pinfunction "S_2") (pintype "passive"))
      (node (ref "Q4") (pin "2") (pinfunction "S_2") (pintype "passive"))
      (node (ref "Q5") (pin "2") (pinfunction "S_2") (pintype "passive"))
      (node (ref "Q6") (pin "2") (pinfunction "S_2") (pintype "passive"))
      (node (ref "R14") (pin "1") (pinfunction "1_1") (pintype "passive"))
      (node (ref "R15") (pin "1") (pinfunction "1_1") (pintype "passive"))
      (node (ref "R16") (pin "1") (pinfunction "1_1") (pintype "passive"))
      (node (ref "R17") (pin "1") (pinfunction "1_1") (pintype "passive"))
      (node (ref "R25") (pin "1") (pinfunction "1_1") (pintype "passive"))
      (node (ref "R26") (pin "1") (pinfunction "1_1") (pintype "passive"))
      (node (ref "R5") (pin "1") (pinfunction "1_1") (pintype "passive"))
      (node (ref "R6") (pin "1") (pinfunction "1_1") (pintype "passive"))
      (node (ref "R7") (pin "1") (pinfunction "1_1") (pintype "passive"))
      (node (ref "TP1") (pin "1") (pinfunction "1_1") (pintype "passive"))
      (node (ref "U1") (pin "11") (pinfunction "S2_11") (pintype "passive"))
      (node (ref "U1") (pin "12") (pinfunction "R2_12") (pintype "passive"))
      (node (ref "U1") (pin "14") (pinfunction "R3_14") (pintype "passive"))
      (node (ref "U1") (pin "15") (pinfunction "S3_15") (pintype "passive"))
      (node (ref "U1") (pin "6") (pinfunction "R1_6") (pintype "passive"))
      (node (ref "U1") (pin "7") (pinfunction "S1_7") (pintype "passive"))
      (node (ref "U1") (pin "8") (pinfunction "GND_8") (pintype "passive"))
      (node (ref "U2") (pin "2") (pinfunction "GND_2") (pintype "passive"))
      (node (ref "U3") (pin "2") (pinfunction "GND_2") (pintype "passive"))
      (node (ref "U4") (pin "2") (pinfunction "GND_2") (pintype "passive"))
    )
    (net (code "16") (name "GND_EXT") (class "Default")
      (node (ref "C7") (pin "1") (pinfunction "1_1") (pintype "passive"))
      (node (ref "D4") (pin "2") (pinfunction "2_2") (pintype "passive"))
      (node (ref "D5") (pin "2") (pinfunction "i/o_2") (pintype "passive"))
      (node (ref "D6") (pin "2") (pinfunction "i/o_2") (pintype "passive"))
      (node (ref "ISO1") (pin "4") (pinfunction "AGND_4") (pintype "passive"))
      (node (ref "J7") (pin "4") (pinfunction "4_4") (pintype "passive"))
      (node (ref "TP2") (pin "1") (pinfunction "1_1") (pintype "passive"))
    )
    (net (code "17") (name "Net-(D2-PadA)") (class "Default")
      (node (ref "D2") (pin "A") (pinfunction "A_A") (pintype "passive"))
      (node (ref "R13") (pin "2") (pinfunction "2_2") (pintype "passive"))
    )
    (net (code "18") (name "Net-(FH1-Pad1)") (class "Default")
      (node (ref "FH1") (pin "1") (pinfunction "1_1") (pintype "passive"))
      (node (ref "J2") (pin "1") (pintype "passive"))
    )
    (net (code "19") (name "Net-(Q2-D)") (class "Default")
      (node (ref "Q2") (pin "3") (pinfunction "D_3") (pintype "passive"))
      (node (ref "R3") (pin "1") (pinfunction "1_1") (pintype "passive"))
      (node (ref "R4") (pin "2") (pinfunction "2_2") (pintype "passive"))
    )
    (net (code "20") (name "Net-(Q2-G)") (class "Default")
      (node (ref "Q2") (pin "1") (pinfunction "G_1") (pintype "passive"))
      (node (ref "Q3") (pin "3") (pinfunction "D_3") (pintype "passive"))
      (node (ref "R2") (pin "1") (pinfunction "1_1") (pintype "passive"))
    )
    (net (code "21") (name "Net-(Q3-G)") (class "Default")
      (node (ref "C2") (pin "2") (pinfunction "2_2") (pintype "passive"))
      (node (ref "Q3") (pin "1") (pinfunction "G_1") (pintype "passive"))
      (node (ref "R1") (pin "1") (pinfunction "1_1") (pintype "passive"))
      (node (ref "R5") (pin "2") (pinfunction "2_2") (pintype "passive"))
    )
    (net (code "22") (name "Net-(Q5-D)") (class "Default")
      (node (ref "D2") (pin "K") (pinfunction "K_K") (pintype "passive"))
      (node (ref "Q5") (pin "3") (pinfunction "D_3") (pintype "passive"))
    )
    (net (code "23") (name "Net-(Q6-G)") (class "Default")
      (node (ref "D3") (pin "A") (pinfunction "A_A") (pintype "passive"))
      (node (ref "Q6") (pin "1") (pinfunction "G_1") (pintype "passive"))
      (node (ref "R19") (pin "1") (pinfunction "1_1") (pintype "passive"))
    )
    (net (code "24") (name "Net-(U3-INA+)") (class "Default")
      (node (ref "R10") (pin "1") (pinfunction "1_1") (pintype "passive"))
      (node (ref "R14") (pin "2") (pinfunction "2_2") (pintype "passive"))
      (node (ref "R17") (pin "2") (pinfunction "2_2") (pintype "passive"))
      (node (ref "U3") (pin "3") (pinfunction "INA+_3") (pintype "passive"))
    )
    (net (code "25") (name "Net-(U3-INB-)") (class "Default")
      (node (ref "R16") (pin "2") (pinfunction "2_2") (pintype "passive"))
      (node (ref "R26") (pin "2") (pinfunction "2_2") (pintype "passive"))
      (node (ref "R9") (pin "1") (pinfunction "1_1") (pintype "passive"))
      (node (ref "U3") (pin "4") (pinfunction "INB-_4") (pintype "passive"))
    )
    (net (code "26") (name "Net-(U4-AIN)") (class "Default")
      (node (ref "R24") (pin "1") (pinfunction "1_1") (pintype "passive"))
      (node (ref "R25") (pin "2") (pinfunction "2_2") (pintype "passive"))
      (node (ref "U4") (pin "3") (pinfunction "AIN_3") (pintype "passive"))
    )
    (net (code "27") (name "VBAT") (class "Default")
      (node (ref "C5") (pin "2") (pinfunction "2_2") (pintype "passive"))
      (node (ref "D1") (pin "1") (pinfunction "1_1") (pintype "passive"))
      (node (ref "FH2") (pin "1") (pinfunction "1_1") (pintype "passive"))
      (node (ref "R10") (pin "2") (pinfunction "2_2") (pintype "passive"))
      (node (ref "R24") (pin "2") (pinfunction "2_2") (pintype "passive"))
      (node (ref "R9") (pin "2") (pinfunction "2_2") (pintype "passive"))
      (node (ref "U2") (pin "1") (pinfunction "VIN_1") (pintype "passive"))
    )
    (net (code "28") (name "VCC_EXT") (class "Default")
      (node (ref "C7") (pin "2") (pinfunction "2_2") (pintype "passive"))
      (node (ref "D4") (pin "1") (pinfunction "1_1") (pintype "passive"))
      (node (ref "ISO1") (pin "1") (pinfunction "AVDD_1") (pintype "passive"))
      (node (ref "J7") (pin "1") (pinfunction "1_1") (pintype "passive"))
      (node (ref "R20") (pin "2") (pinfunction "2_2") (pintype "passive"))
      (node (ref "R21") (pin "2") (pinfunction "2_2") (pintype "passive"))
    )
    (net (code "29") (name "unconnected-(MTH1-Pad1)") (class "Default")
      (node (ref "MTH1") (pin "1") (pinfunction "1_1") (pintype "passive+no_connect"))
    )
    (net (code "30") (name "unconnected-(MTH2-Pad1)") (class "Default")
      (node (ref "MTH2") (pin "1") (pinfunction "1_1") (pintype "passive+no_connect"))
    )
    (net (code "31") (name "unconnected-(MTH3-Pad1)") (class "Default")
      (node (ref "MTH3") (pin "1") (pinfunction "1_1") (pintype "passive+no_connect"))
    )
    (net (code "32") (name "unconnected-(MTH4-Pad1)") (class "Default")
      (node (ref "MTH4") (pin "1") (pinfunction "1_1") (pintype "passive+no_connect"))
    )
    (net (code "33") (name "unconnected-(R14-Pad3)") (class "Default")
      (node (ref "R14") (pin "3") (pinfunction "3_3") (pintype "passive+no_connect"))
    )
    (net (code "34") (name "unconnected-(R26-Pad3)") (class "Default")
      (node (ref "R26") (pin "3") (pinfunction "3_3") (pintype "passive+no_connect"))
    )
    (net (code "35") (name "unconnected-(U1-NC-Pad2)") (class "Default")
      (node (ref "U1") (pin "2") (pinfunction "NC_2") (pintype "passive+no_connect"))
    )
    (net (code "36") (name "unconnected-(U1-Q1-Pad9)") (class "Default")
      (node (ref "U1") (pin "9") (pinfunction "Q1_9") (pintype "passive+no_connect"))
    )
    (net (code "37") (name "unconnected-(U1-Q2-Pad10)") (class "Default")
      (node (ref "U1") (pin "10") (pinfunction "Q2_10") (pintype "passive+no_connect"))
    )
    (net (code "38") (name "unconnected-(U1-Q3-Pad1)") (class "Default")
      (node (ref "U1") (pin "1") (pinfunction "Q3_1") (pintype "passive+no_connect"))
    )
    (net (code "39") (name "unconnected-(U2-EN-Pad4)") (class "Default")
      (node (ref "U2") (pin "4") (pinfunction "EN_4") (pintype "passive+no_connect"))
    )
  )
)
